# connectors.net
KiCad netlist of a schematic drawn in EAGLE
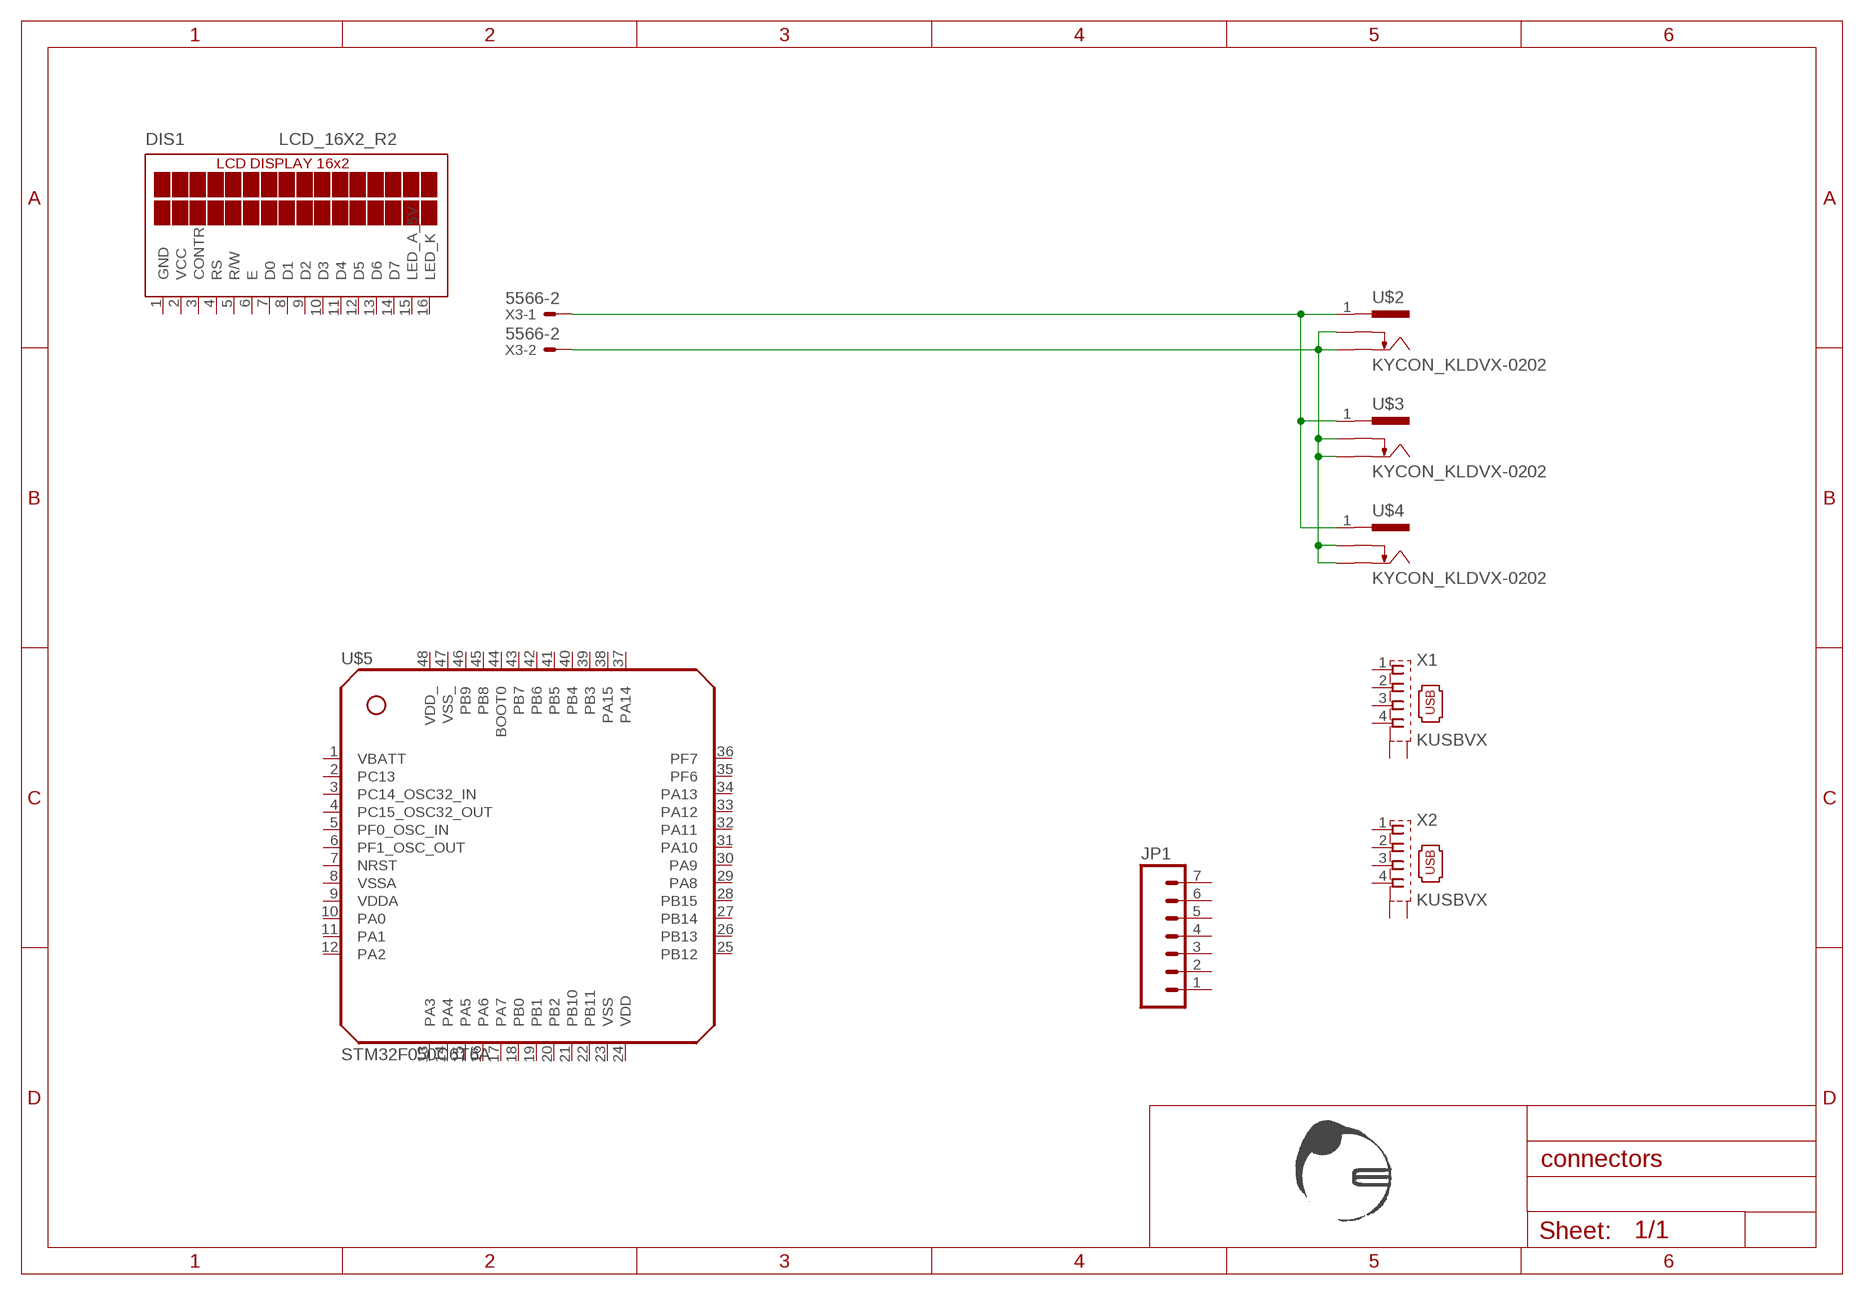
[diagram p0: schematic, sheet 1]

(export (version "E")
  (design (tool "Eeschema 10.0.6"))
  (components
    (comp (ref "DIS1")
      (value "LCD_16X2_R2")
      (footprint "eagle-import:LCD_16X2_R2")
      (libsource (lib "eagle-import") (part "LCD_16X2_R2"))
    )
    (comp (ref "JP1")
      (value "M07")
      (footprint "eagle-import:1X07")
      (libsource (lib "eagle-import") (part "M07"))
    )
    (comp (ref "U$1")
      (value "EQUINOX_LOGO_SMALL")
      (footprint "eagle-import:EQUINOX_LOGO_SMALL")
      (libsource (lib "eagle-import") (part "EQUINOX_LOGO_SMALL"))
    )
    (comp (ref "U$2")
      (value "KYCON_KLDVX-0202")
      (footprint "eagle-import:KYCON_KLVDX_2020_B")
      (libsource (lib "eagle-import") (part "KYCON_KLDVX-0202"))
    )
    (comp (ref "U$3")
      (value "KYCON_KLDVX-0202")
      (footprint "eagle-import:KYCON_KLVDX_2020_B")
      (libsource (lib "eagle-import") (part "KYCON_KLDVX-0202"))
    )
    (comp (ref "U$4")
      (value "KYCON_KLDVX-0202")
      (footprint "eagle-import:KYCON_KLVDX_2020_B")
      (libsource (lib "eagle-import") (part "KYCON_KLDVX-0202"))
    )
    (comp (ref "U$5")
      (value "STM32F050C6T6A")
      (footprint "eagle-import:LQFP48")
      (libsource (lib "eagle-import") (part "STM32F050C6T6A"))
    )
    (comp (ref "X1")
      (value "KUSBVX")
      (footprint "eagle-import:KUSBVX")
      (libsource (lib "eagle-import") (part "KUSBVX"))
    )
    (comp (ref "X2")
      (value "KUSBVX")
      (footprint "eagle-import:KUSBVX")
      (libsource (lib "eagle-import") (part "KUSBVX"))
    )
    (comp (ref "X3")
      (value "5566-2")
      (footprint "eagle-import:5566-2")
      (libsource (lib "eagle-import") (part "5566-2"))
    )
  )
  (nets
    (net (code "1") (name "/GND") (class "Default")
      (node (ref "DIS1") (pin "1") (pinfunction "GND_1") (pintype "power_in"))
    )
    (net (code "2") (name "/VCC") (class "Default")
      (node (ref "DIS1") (pin "2") (pinfunction "VCC_2") (pintype "power_in"))
    )
    (net (code "3") (name "/VDD") (class "Default")
      (node (ref "U$5") (pin "24") (pinfunction "VDD_24") (pintype "power_in"))
    )
    (net (code "4") (name "/VDD_") (class "Default")
      (node (ref "U$5") (pin "48") (pinfunction "VDD__48") (pintype "power_in"))
    )
    (net (code "5") (name "/VSS") (class "Default")
      (node (ref "U$5") (pin "23") (pinfunction "VSS_23") (pintype "power_in"))
    )
    (net (code "6") (name "/VSS_") (class "Default")
      (node (ref "U$5") (pin "47") (pinfunction "VSS__47") (pintype "power_in"))
    )
    (net (code "7") (name "Net-(U$2-PAD1)") (class "Default")
      (node (ref "U$2") (pin "1") (pinfunction "PAD1_1") (pintype "passive"))
      (node (ref "U$3") (pin "1") (pinfunction "PAD1_1") (pintype "passive"))
      (node (ref "U$4") (pin "1") (pinfunction "PAD1_1") (pintype "passive"))
      (node (ref "X3") (pin "1") (pinfunction "S_1") (pintype "passive"))
    )
    (net (code "8") (name "Net-(U$2-PAD2)") (class "Default")
      (node (ref "U$2") (pin "2") (pinfunction "PAD2_2") (pintype "passive"))
      (node (ref "U$2") (pin "3") (pinfunction "PAD3_3") (pintype "passive"))
      (node (ref "U$3") (pin "2") (pinfunction "PAD2_2") (pintype "passive"))
      (node (ref "U$3") (pin "3") (pinfunction "PAD3_3") (pintype "passive"))
      (node (ref "U$4") (pin "2") (pinfunction "PAD2_2") (pintype "passive"))
      (node (ref "U$4") (pin "3") (pinfunction "PAD3_3") (pintype "passive"))
      (node (ref "X3") (pin "2") (pinfunction "S_2") (pintype "passive"))
    )
    (net (code "9") (name "unconnected-(DIS1-CONTR-Pad3)") (class "Default")
      (node (ref "DIS1") (pin "3") (pinfunction "CONTR_3") (pintype "input"))
    )
    (net (code "10") (name "unconnected-(DIS1-D0-Pad7)") (class "Default")
      (node (ref "DIS1") (pin "7") (pinfunction "D0_7") (pintype "input"))
    )
    (net (code "11") (name "unconnected-(DIS1-D1-Pad8)") (class "Default")
      (node (ref "DIS1") (pin "8") (pinfunction "D1_8") (pintype "input"))
    )
    (net (code "12") (name "unconnected-(DIS1-D2-Pad9)") (class "Default")
      (node (ref "DIS1") (pin "9") (pinfunction "D2_9") (pintype "input"))
    )
    (net (code "13") (name "unconnected-(DIS1-D3-Pad10)") (class "Default")
      (node (ref "DIS1") (pin "10") (pinfunction "D3_10") (pintype "input"))
    )
    (net (code "14") (name "unconnected-(DIS1-D4-Pad11)") (class "Default")
      (node (ref "DIS1") (pin "11") (pinfunction "D4_11") (pintype "input"))
    )
    (net (code "15") (name "unconnected-(DIS1-D5-Pad12)") (class "Default")
      (node (ref "DIS1") (pin "12") (pinfunction "D5_12") (pintype "input"))
    )
    (net (code "16") (name "unconnected-(DIS1-D6-Pad13)") (class "Default")
      (node (ref "DIS1") (pin "13") (pinfunction "D6_13") (pintype "input"))
    )
    (net (code "17") (name "unconnected-(DIS1-D7-Pad14)") (class "Default")
      (node (ref "DIS1") (pin "14") (pinfunction "D7_14") (pintype "input"))
    )
    (net (code "18") (name "unconnected-(DIS1-E-Pad6)") (class "Default")
      (node (ref "DIS1") (pin "6") (pinfunction "E_6") (pintype "input"))
    )
    (net (code "19") (name "unconnected-(DIS1-LED_A_5V-Pad15)") (class "Default")
      (node (ref "DIS1") (pin "15") (pinfunction "LED_A_5V_15") (pintype "no_connect"))
    )
    (net (code "20") (name "unconnected-(DIS1-LED_K-Pad16)") (class "Default")
      (node (ref "DIS1") (pin "16") (pinfunction "LED_K_16") (pintype "no_connect"))
    )
    (net (code "21") (name "unconnected-(DIS1-RS-Pad4)") (class "Default")
      (node (ref "DIS1") (pin "4") (pinfunction "RS_4") (pintype "input"))
    )
    (net (code "22") (name "unconnected-(DIS1-R{slash}W-Pad5)") (class "Default")
      (node (ref "DIS1") (pin "5") (pinfunction "R/W_5") (pintype "input"))
    )
    (net (code "23") (name "unconnected-(JP1-Pad1)") (class "Default")
      (node (ref "JP1") (pin "1") (pinfunction "1_1") (pintype "passive"))
    )
    (net (code "24") (name "unconnected-(JP1-Pad2)") (class "Default")
      (node (ref "JP1") (pin "2") (pinfunction "2_2") (pintype "passive"))
    )
    (net (code "25") (name "unconnected-(JP1-Pad3)") (class "Default")
      (node (ref "JP1") (pin "3") (pinfunction "3_3") (pintype "passive"))
    )
    (net (code "26") (name "unconnected-(JP1-Pad4)") (class "Default")
      (node (ref "JP1") (pin "4") (pinfunction "4_4") (pintype "passive"))
    )
    (net (code "27") (name "unconnected-(JP1-Pad5)") (class "Default")
      (node (ref "JP1") (pin "5") (pinfunction "5_5") (pintype "passive"))
    )
    (net (code "28") (name "unconnected-(JP1-Pad6)") (class "Default")
      (node (ref "JP1") (pin "6") (pinfunction "6_6") (pintype "passive"))
    )
    (net (code "29") (name "unconnected-(JP1-Pad7)") (class "Default")
      (node (ref "JP1") (pin "7") (pinfunction "7_7") (pintype "passive"))
    )
    (net (code "30") (name "unconnected-(U$5-BOOT0-Pad44)") (class "Default")
      (node (ref "U$5") (pin "44") (pinfunction "BOOT0_44") (pintype "bidirectional"))
    )
    (net (code "31") (name "unconnected-(U$5-NRST-Pad7)") (class "Default")
      (node (ref "U$5") (pin "7") (pinfunction "NRST_7") (pintype "bidirectional"))
    )
    (net (code "32") (name "unconnected-(U$5-PA0-Pad10)") (class "Default")
      (node (ref "U$5") (pin "10") (pinfunction "PA0_10") (pintype "bidirectional"))
    )
    (net (code "33") (name "unconnected-(U$5-PA1-Pad11)") (class "Default")
      (node (ref "U$5") (pin "11") (pinfunction "PA1_11") (pintype "bidirectional"))
    )
    (net (code "34") (name "unconnected-(U$5-PA2-Pad12)") (class "Default")
      (node (ref "U$5") (pin "12") (pinfunction "PA2_12") (pintype "bidirectional"))
    )
    (net (code "35") (name "unconnected-(U$5-PA3-Pad13)") (class "Default")
      (node (ref "U$5") (pin "13") (pinfunction "PA3_13") (pintype "bidirectional"))
    )
    (net (code "36") (name "unconnected-(U$5-PA4-Pad14)") (class "Default")
      (node (ref "U$5") (pin "14") (pinfunction "PA4_14") (pintype "bidirectional"))
    )
    (net (code "37") (name "unconnected-(U$5-PA5-Pad15)") (class "Default")
      (node (ref "U$5") (pin "15") (pinfunction "PA5_15") (pintype "bidirectional"))
    )
    (net (code "38") (name "unconnected-(U$5-PA6-Pad16)") (class "Default")
      (node (ref "U$5") (pin "16") (pinfunction "PA6_16") (pintype "bidirectional"))
    )
    (net (code "39") (name "unconnected-(U$5-PA7-Pad17)") (class "Default")
      (node (ref "U$5") (pin "17") (pinfunction "PA7_17") (pintype "bidirectional"))
    )
    (net (code "40") (name "unconnected-(U$5-PA8-Pad29)") (class "Default")
      (node (ref "U$5") (pin "29") (pinfunction "PA8_29") (pintype "bidirectional"))
    )
    (net (code "41") (name "unconnected-(U$5-PA9-Pad30)") (class "Default")
      (node (ref "U$5") (pin "30") (pinfunction "PA9_30") (pintype "bidirectional"))
    )
    (net (code "42") (name "unconnected-(U$5-PA10-Pad31)") (class "Default")
      (node (ref "U$5") (pin "31") (pinfunction "PA10_31") (pintype "bidirectional"))
    )
    (net (code "43") (name "unconnected-(U$5-PA11-Pad32)") (class "Default")
      (node (ref "U$5") (pin "32") (pinfunction "PA11_32") (pintype "bidirectional"))
    )
    (net (code "44") (name "unconnected-(U$5-PA12-Pad33)") (class "Default")
      (node (ref "U$5") (pin "33") (pinfunction "PA12_33") (pintype "bidirectional"))
    )
    (net (code "45") (name "unconnected-(U$5-PA13-Pad34)") (class "Default")
      (node (ref "U$5") (pin "34") (pinfunction "PA13_34") (pintype "bidirectional"))
    )
    (net (code "46") (name "unconnected-(U$5-PA14-Pad37)") (class "Default")
      (node (ref "U$5") (pin "37") (pinfunction "PA14_37") (pintype "bidirectional"))
    )
    (net (code "47") (name "unconnected-(U$5-PA15-Pad38)") (class "Default")
      (node (ref "U$5") (pin "38") (pinfunction "PA15_38") (pintype "bidirectional"))
    )
    (net (code "48") (name "unconnected-(U$5-PB0-Pad18)") (class "Default")
      (node (ref "U$5") (pin "18") (pinfunction "PB0_18") (pintype "bidirectional"))
    )
    (net (code "49") (name "unconnected-(U$5-PB1-Pad19)") (class "Default")
      (node (ref "U$5") (pin "19") (pinfunction "PB1_19") (pintype "bidirectional"))
    )
    (net (code "50") (name "unconnected-(U$5-PB2-Pad20)") (class "Default")
      (node (ref "U$5") (pin "20") (pinfunction "PB2_20") (pintype "bidirectional"))
    )
    (net (code "51") (name "unconnected-(U$5-PB3-Pad39)") (class "Default")
      (node (ref "U$5") (pin "39") (pinfunction "PB3_39") (pintype "bidirectional"))
    )
    (net (code "52") (name "unconnected-(U$5-PB4-Pad40)") (class "Default")
      (node (ref "U$5") (pin "40") (pinfunction "PB4_40") (pintype "bidirectional"))
    )
    (net (code "53") (name "unconnected-(U$5-PB5-Pad41)") (class "Default")
      (node (ref "U$5") (pin "41") (pinfunction "PB5_41") (pintype "bidirectional"))
    )
    (net (code "54") (name "unconnected-(U$5-PB6-Pad42)") (class "Default")
      (node (ref "U$5") (pin "42") (pinfunction "PB6_42") (pintype "bidirectional"))
    )
    (net (code "55") (name "unconnected-(U$5-PB7-Pad43)") (class "Default")
      (node (ref "U$5") (pin "43") (pinfunction "PB7_43") (pintype "bidirectional"))
    )
    (net (code "56") (name "unconnected-(U$5-PB8-Pad45)") (class "Default")
      (node (ref "U$5") (pin "45") (pinfunction "PB8_45") (pintype "bidirectional"))
    )
    (net (code "57") (name "unconnected-(U$5-PB9-Pad46)") (class "Default")
      (node (ref "U$5") (pin "46") (pinfunction "PB9_46") (pintype "bidirectional"))
    )
    (net (code "58") (name "unconnected-(U$5-PB10-Pad21)") (class "Default")
      (node (ref "U$5") (pin "21") (pinfunction "PB10_21") (pintype "bidirectional"))
    )
    (net (code "59") (name "unconnected-(U$5-PB11-Pad22)") (class "Default")
      (node (ref "U$5") (pin "22") (pinfunction "PB11_22") (pintype "bidirectional"))
    )
    (net (code "60") (name "unconnected-(U$5-PB12-Pad25)") (class "Default")
      (node (ref "U$5") (pin "25") (pinfunction "PB12_25") (pintype "bidirectional"))
    )
    (net (code "61") (name "unconnected-(U$5-PB13-Pad26)") (class "Default")
      (node (ref "U$5") (pin "26") (pinfunction "PB13_26") (pintype "bidirectional"))
    )
    (net (code "62") (name "unconnected-(U$5-PB14-Pad27)") (class "Default")
      (node (ref "U$5") (pin "27") (pinfunction "PB14_27") (pintype "bidirectional"))
    )
    (net (code "63") (name "unconnected-(U$5-PB15-Pad28)") (class "Default")
      (node (ref "U$5") (pin "28") (pinfunction "PB15_28") (pintype "bidirectional"))
    )
    (net (code "64") (name "unconnected-(U$5-PC13-Pad2)") (class "Default")
      (node (ref "U$5") (pin "2") (pinfunction "PC13_2") (pintype "bidirectional"))
    )
    (net (code "65") (name "unconnected-(U$5-PC14_OSC32_IN-Pad3)") (class "Default")
      (node (ref "U$5") (pin "3") (pinfunction "PC14_OSC32_IN_3") (pintype "bidirectional"))
    )
    (net (code "66") (name "unconnected-(U$5-PC15_OSC32_OUT-Pad4)") (class "Default")
      (node (ref "U$5") (pin "4") (pinfunction "PC15_OSC32_OUT_4") (pintype "bidirectional"))
    )
    (net (code "67") (name "unconnected-(U$5-PF0_OSC_IN-Pad5)") (class "Default")
      (node (ref "U$5") (pin "5") (pinfunction "PF0_OSC_IN_5") (pintype "bidirectional"))
    )
    (net (code "68") (name "unconnected-(U$5-PF1_OSC_OUT-Pad6)") (class "Default")
      (node (ref "U$5") (pin "6") (pinfunction "PF1_OSC_OUT_6") (pintype "input"))
    )
    (net (code "69") (name "unconnected-(U$5-PF6-Pad35)") (class "Default")
      (node (ref "U$5") (pin "35") (pinfunction "PF6_35") (pintype "bidirectional"))
    )
    (net (code "70") (name "unconnected-(U$5-PF7-Pad36)") (class "Default")
      (node (ref "U$5") (pin "36") (pinfunction "PF7_36") (pintype "bidirectional"))
    )
    (net (code "71") (name "unconnected-(U$5-VBATT-Pad1)") (class "Default")
      (node (ref "U$5") (pin "1") (pinfunction "VBATT_1") (pintype "bidirectional"))
    )
    (net (code "72") (name "unconnected-(U$5-VDDA-Pad9)") (class "Default")
      (node (ref "U$5") (pin "9") (pinfunction "VDDA_9") (pintype "bidirectional"))
    )
    (net (code "73") (name "unconnected-(U$5-VSSA-Pad8)") (class "Default")
      (node (ref "U$5") (pin "8") (pinfunction "VSSA_8") (pintype "bidirectional"))
    )
    (net (code "74") (name "unconnected-(X1-Pad1)") (class "Default")
      (node (ref "X1") (pin "1") (pinfunction "1_1") (pintype "passive"))
    )
    (net (code "75") (name "unconnected-(X1-Pad2)") (class "Default")
      (node (ref "X1") (pin "2") (pinfunction "2_2") (pintype "passive"))
    )
    (net (code "76") (name "unconnected-(X1-Pad3)") (class "Default")
      (node (ref "X1") (pin "3") (pinfunction "3_3") (pintype "passive"))
    )
    (net (code "77") (name "unconnected-(X1-Pad4)") (class "Default")
      (node (ref "X1") (pin "4") (pinfunction "4_4") (pintype "passive"))
    )
    (net (code "78") (name "unconnected-(X1-S1-PadM1)") (class "Default")
      (node (ref "X1") (pin "M1") (pinfunction "S1_M1") (pintype "passive"))
    )
    (net (code "79") (name "unconnected-(X1-S2-PadM2)") (class "Default")
      (node (ref "X1") (pin "M2") (pinfunction "S2_M2") (pintype "passive"))
    )
    (net (code "80") (name "unconnected-(X2-Pad1)") (class "Default")
      (node (ref "X2") (pin "1") (pinfunction "1_1") (pintype "passive"))
    )
    (net (code "81") (name "unconnected-(X2-Pad2)") (class "Default")
      (node (ref "X2") (pin "2") (pinfunction "2_2") (pintype "passive"))
    )
    (net (code "82") (name "unconnected-(X2-Pad3)") (class "Default")
      (node (ref "X2") (pin "3") (pinfunction "3_3") (pintype "passive"))
    )
    (net (code "83") (name "unconnected-(X2-Pad4)") (class "Default")
      (node (ref "X2") (pin "4") (pinfunction "4_4") (pintype "passive"))
    )
    (net (code "84") (name "unconnected-(X2-S1-PadM1)") (class "Default")
      (node (ref "X2") (pin "M1") (pinfunction "S1_M1") (pintype "passive"))
    )
    (net (code "85") (name "unconnected-(X2-S2-PadM2)") (class "Default")
      (node (ref "X2") (pin "M2") (pinfunction "S2_M2") (pintype "passive"))
    )
  )
)
